# eink_r1.net
KiCad netlist of a schematic drawn in Altium Designer
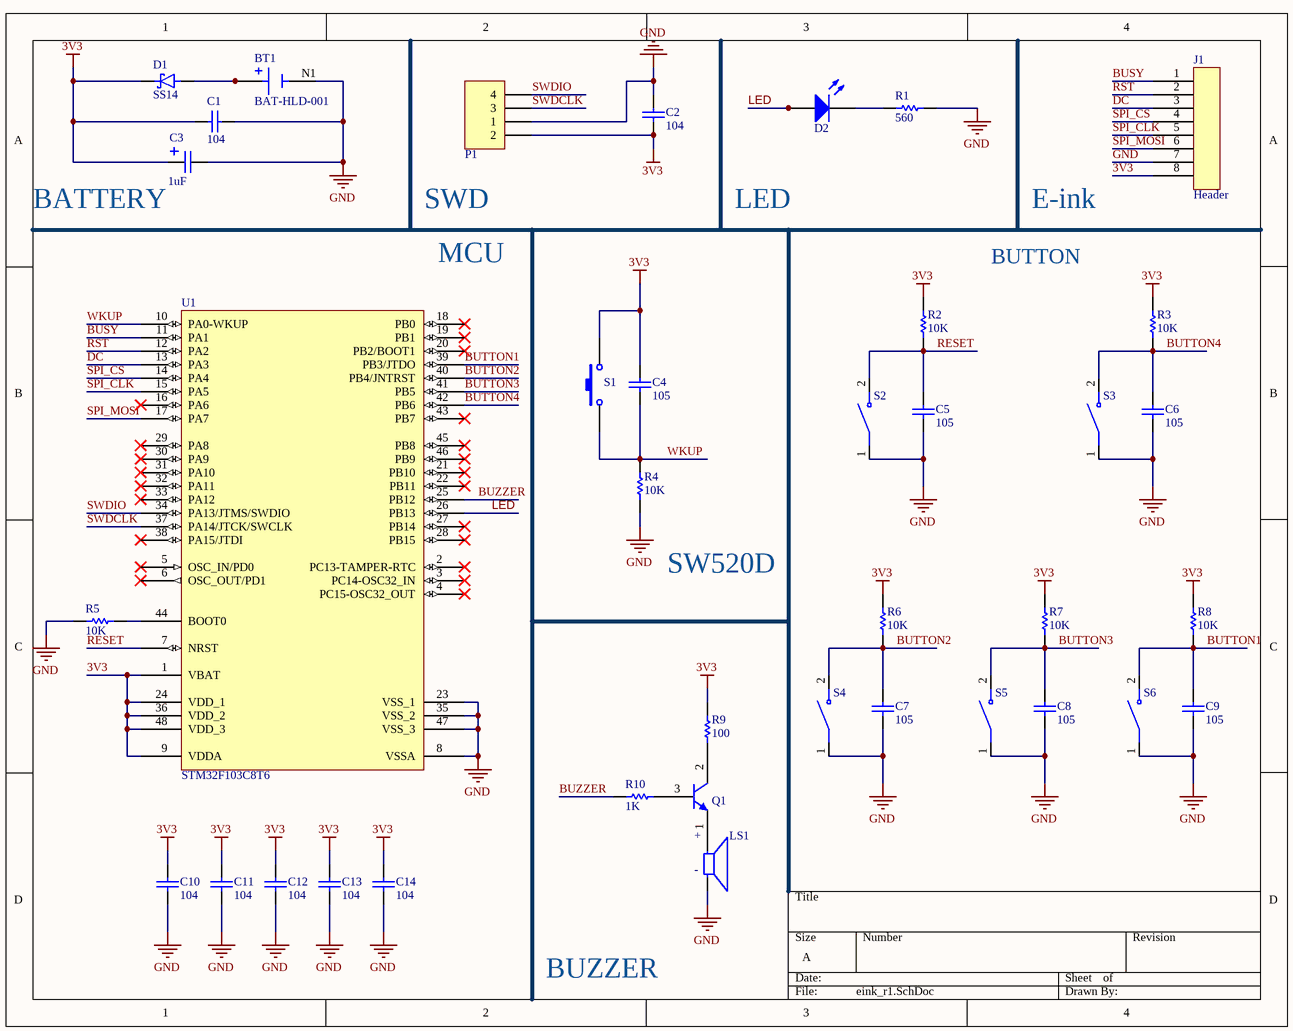
[diagram p0: eink_r1.SchDoc]

(export (version "E")
  (design (tool "Eeschema 10.0.6"))
  (components
    (comp (ref "BT1")
      (value "BAT-HLD-001")
      (footprint "BAT_BAT-HLD-001")
      (description "Battery Retainer Coin, 20.0mm 1 Cell SMD (SMT) Tab")
      (libsource (lib "BAT-HLD-001") (part "BAT-HLD-001"))
    )
    (comp (ref "C1")
      (value "104")
      (footprint "CAP-SM-0603")
      (description "Capacitor")
      (fields (field (name "Comment") "Cap Non-Pol SMD"))
      (libsource (lib "PIF_Library") (part "Cap Non-Pol SMD"))
    )
    (comp (ref "C2")
      (value "104")
      (footprint "CAP-SM-0603")
      (description "Capacitor")
      (fields (field (name "Comment") "Cap Non-Pol SMD"))
      (libsource (lib "PIF_Library") (part "Cap Non-Pol SMD"))
    )
    (comp (ref "C3")
      (value "1uF")
      (footprint "CAPMP3216X18N")
      (fields (field (name "Comment") "Tantalum Capacitor"))
      (libsource (lib "MiclsLib") (part "Tantalum Capacitor"))
    )
    (comp (ref "C4")
      (value "105")
      (footprint "CAP-SM-0603")
      (description "Capacitor")
      (fields (field (name "Comment") "Cap Non-Pol SMD"))
      (libsource (lib "PIF_Library") (part "Cap Non-Pol SMD"))
    )
    (comp (ref "C5")
      (value "105")
      (footprint "CAP-SM-0603")
      (description "Capacitor")
      (fields (field (name "Comment") "Cap Non-Pol SMD"))
      (libsource (lib "PIF_Library") (part "Cap Non-Pol SMD"))
    )
    (comp (ref "C6")
      (value "105")
      (footprint "CAP-SM-0603")
      (description "Capacitor")
      (fields (field (name "Comment") "Cap Non-Pol SMD"))
      (libsource (lib "PIF_Library") (part "Cap Non-Pol SMD"))
    )
    (comp (ref "C7")
      (value "105")
      (footprint "CAP-SM-0603")
      (description "Capacitor")
      (fields (field (name "Comment") "Cap Non-Pol SMD"))
      (libsource (lib "PIF_Library") (part "Cap Non-Pol SMD"))
    )
    (comp (ref "C8")
      (value "105")
      (footprint "CAP-SM-0603")
      (description "Capacitor")
      (fields (field (name "Comment") "Cap Non-Pol SMD"))
      (libsource (lib "PIF_Library") (part "Cap Non-Pol SMD"))
    )
    (comp (ref "C9")
      (value "105")
      (footprint "CAP-SM-0603")
      (description "Capacitor")
      (fields (field (name "Comment") "Cap Non-Pol SMD"))
      (libsource (lib "PIF_Library") (part "Cap Non-Pol SMD"))
    )
    (comp (ref "C10")
      (value "104")
      (footprint "CAP-SM-0603")
      (description "Capacitor")
      (fields (field (name "Comment") "Cap Non-Pol SMD"))
      (libsource (lib "PIF_Library") (part "Cap Non-Pol SMD"))
    )
    (comp (ref "C11")
      (value "104")
      (footprint "CAP-SM-0603")
      (description "Capacitor")
      (fields (field (name "Comment") "Cap Non-Pol SMD"))
      (libsource (lib "PIF_Library") (part "Cap Non-Pol SMD"))
    )
    (comp (ref "C12")
      (value "104")
      (footprint "CAP-SM-0603")
      (description "Capacitor")
      (fields (field (name "Comment") "Cap Non-Pol SMD"))
      (libsource (lib "PIF_Library") (part "Cap Non-Pol SMD"))
    )
    (comp (ref "C13")
      (value "104")
      (footprint "CAP-SM-0603")
      (description "Capacitor")
      (fields (field (name "Comment") "Cap Non-Pol SMD"))
      (libsource (lib "PIF_Library") (part "Cap Non-Pol SMD"))
    )
    (comp (ref "C14")
      (value "104")
      (footprint "CAP-SM-0603")
      (description "Capacitor")
      (fields (field (name "Comment") "Cap Non-Pol SMD"))
      (libsource (lib "PIF_Library") (part "Cap Non-Pol SMD"))
    )
    (comp (ref "D1") (value "SS14") (footprint "DIOM4325X250N") (libsource (lib "SS14") (part "SS14")))
    (comp (ref "D2")
      (value "LED SMD")
      (footprint "LED_0603_Blue")
      (description "LED")
      (libsource (lib "PIF_Library") (part "LED SMD"))
    )
    (comp (ref "J1")
      (value "Header")
      (footprint "PCBComponent_1")
      (description "XH 2.54mm PCB Header 8 Pin SMD Horizontal")
      (libsource (lib "XH-8A_SMD_Header") (part "Header"))
    )
    (comp (ref "LS1")
      (value "CMT-0926-86-SMT-TR")
      (footprint "XDCR_CMT-0926-86-SMT-TR")
      (libsource (lib "CMT-0926-86-SMT-TR") (part "CMT-0926-86-SMT-TR"))
    )
    (comp (ref "P1")
      (value "Header 4H")
      (footprint "JP4H")
      (description "Header, 4-Pin, Right Angle")
      (fields (field (name "PUBLISHER") "Altium Limited"))
      (libsource (lib "PIF_Library") (part "Header 4H"))
    )
    (comp (ref "Q1")
      (value "C1815")
      (footprint "SOT23B")
      (description "NPN Bipolar Transistor")
      (libsource (lib "PIF_Library") (part "C1815"))
    )
    (comp (ref "R1")
      (value "560")
      (footprint "RES-SM-0603")
      (description "Resistor")
      (fields (field (name "Comment") "RESISTOR SMD"))
      (libsource (lib "PIF_Library") (part "RESISTOR SMD"))
    )
    (comp (ref "R2")
      (value "10K")
      (footprint "RES-SM-0603")
      (description "Resistor")
      (fields (field (name "Comment") "RESISTOR SMD"))
      (libsource (lib "PIF_Library") (part "RESISTOR SMD"))
    )
    (comp (ref "R3")
      (value "10K")
      (footprint "RES-SM-0603")
      (description "Resistor")
      (fields (field (name "Comment") "RESISTOR SMD"))
      (libsource (lib "PIF_Library") (part "RESISTOR SMD"))
    )
    (comp (ref "R4")
      (value "10K")
      (footprint "RES-SM-0603")
      (description "Resistor")
      (fields (field (name "Comment") "RESISTOR SMD"))
      (libsource (lib "PIF_Library") (part "RESISTOR SMD"))
    )
    (comp (ref "R5")
      (value "10K")
      (footprint "RES-SM-0603")
      (description "Resistor")
      (fields (field (name "Comment") "RESISTOR SMD"))
      (libsource (lib "PIF_Library") (part "RESISTOR SMD"))
    )
    (comp (ref "R6")
      (value "10K")
      (footprint "RES-SM-0603")
      (description "Resistor")
      (fields (field (name "Comment") "RESISTOR SMD"))
      (libsource (lib "PIF_Library") (part "RESISTOR SMD"))
    )
    (comp (ref "R7")
      (value "10K")
      (footprint "RES-SM-0603")
      (description "Resistor")
      (fields (field (name "Comment") "RESISTOR SMD"))
      (libsource (lib "PIF_Library") (part "RESISTOR SMD"))
    )
    (comp (ref "R8")
      (value "10K")
      (footprint "RES-SM-0603")
      (description "Resistor")
      (fields (field (name "Comment") "RESISTOR SMD"))
      (libsource (lib "PIF_Library") (part "RESISTOR SMD"))
    )
    (comp (ref "R9")
      (value "100")
      (footprint "RES-SM-0603")
      (description "Resistor")
      (fields (field (name "Comment") "RESISTOR SMD"))
      (libsource (lib "PIF_Library") (part "RESISTOR SMD"))
    )
    (comp (ref "R10")
      (value "1K")
      (footprint "RES-SM-0603")
      (description "Resistor")
      (fields (field (name "Comment") "RESISTOR SMD"))
      (libsource (lib "PIF_Library") (part "RESISTOR SMD"))
    )
    (comp (ref "S1")
      (value "Tact SW - 2Pin")
      (footprint "SW2")
      (description "Switch button 2 pin")
      (libsource (lib "PIF_Library") (part "Tact SW - 2Pin"))
    )
    (comp (ref "S2")
      (value "PTS636_SM43J_SMTR_LFS")
      (footprint "SW_PTS636_SM43J_SMTR_LFS")
      (description "Tactile Switch SPST-NO Top Actuated Surface Mount")
      (libsource (lib "PTS636_SM43J_SMTR_LFS") (part "PTS636_SM43J_SMTR_LFS"))
    )
    (comp (ref "S3")
      (value "PTS636_SM43J_SMTR_LFS")
      (footprint "SW_PTS636_SM43J_SMTR_LFS")
      (description "Tactile Switch SPST-NO Top Actuated Surface Mount")
      (libsource (lib "PTS636_SM43J_SMTR_LFS") (part "PTS636_SM43J_SMTR_LFS"))
    )
    (comp (ref "S4")
      (value "PTS636_SM43J_SMTR_LFS")
      (footprint "SW_PTS636_SM43J_SMTR_LFS")
      (description "Tactile Switch SPST-NO Top Actuated Surface Mount")
      (libsource (lib "PTS636_SM43J_SMTR_LFS") (part "PTS636_SM43J_SMTR_LFS"))
    )
    (comp (ref "S5")
      (value "PTS636_SM43J_SMTR_LFS")
      (footprint "SW_PTS636_SM43J_SMTR_LFS")
      (description "Tactile Switch SPST-NO Top Actuated Surface Mount")
      (libsource (lib "PTS636_SM43J_SMTR_LFS") (part "PTS636_SM43J_SMTR_LFS"))
    )
    (comp (ref "S6")
      (value "PTS636_SM43J_SMTR_LFS")
      (footprint "SW_PTS636_SM43J_SMTR_LFS")
      (description "Tactile Switch SPST-NO Top Actuated Surface Mount")
      (libsource (lib "PTS636_SM43J_SMTR_LFS") (part "PTS636_SM43J_SMTR_LFS"))
    )
    (comp (ref "U1")
      (value "STM32F103C8T6")
      (footprint "TSQFP50P900X900X160-48N")
      (fields (field (name "MANUFACTURER") "ST"))
      (libsource (lib "MiclsLib") (part "STM32F103C8T6"))
    )
  )
  (nets
    (net (code "1") (name "/BUSY") (class "Default")
      (node (ref "J1") (pin "1") (pintype "passive"))
      (node (ref "U1") (pin "11") (pinfunction "PA1_11") (pintype "bidirectional"))
    )
    (net (code "2") (name "/BUTTON1") (class "Default")
      (node (ref "C9") (pin "2") (pinfunction "2_2") (pintype "passive"))
      (node (ref "R8") (pin "1") (pinfunction "1_1") (pintype "passive"))
      (node (ref "S6") (pin "2") (pinfunction "NO_2") (pintype "passive"))
      (node (ref "U1") (pin "39") (pinfunction "PB3/JTDO_39") (pintype "bidirectional"))
    )
    (net (code "3") (name "/BUTTON2") (class "Default")
      (node (ref "C7") (pin "2") (pinfunction "2_2") (pintype "passive"))
      (node (ref "R6") (pin "1") (pinfunction "1_1") (pintype "passive"))
      (node (ref "S4") (pin "2") (pinfunction "NO_2") (pintype "passive"))
      (node (ref "U1") (pin "40") (pinfunction "PB4/JNTRST_40") (pintype "bidirectional"))
    )
    (net (code "4") (name "/BUTTON3") (class "Default")
      (node (ref "C8") (pin "2") (pinfunction "2_2") (pintype "passive"))
      (node (ref "R7") (pin "1") (pinfunction "1_1") (pintype "passive"))
      (node (ref "S5") (pin "2") (pinfunction "NO_2") (pintype "passive"))
      (node (ref "U1") (pin "41") (pinfunction "PB5_41") (pintype "bidirectional"))
    )
    (net (code "5") (name "/BUTTON4") (class "Default")
      (node (ref "C6") (pin "2") (pinfunction "2_2") (pintype "passive"))
      (node (ref "R3") (pin "1") (pinfunction "1_1") (pintype "passive"))
      (node (ref "S3") (pin "2") (pinfunction "NO_2") (pintype "passive"))
      (node (ref "U1") (pin "42") (pinfunction "PB6_42") (pintype "bidirectional"))
    )
    (net (code "6") (name "/BUZZER") (class "Default")
      (node (ref "R10") (pin "1") (pinfunction "1_1") (pintype "passive"))
      (node (ref "U1") (pin "25") (pinfunction "PB12_25") (pintype "bidirectional"))
    )
    (net (code "7") (name "/DC") (class "Default")
      (node (ref "J1") (pin "3") (pintype "passive"))
      (node (ref "U1") (pin "13") (pinfunction "PA3_13") (pintype "bidirectional"))
    )
    (net (code "8") (name "/LED") (class "Default")
      (node (ref "D2") (pin "1") (pinfunction "A_1") (pintype "passive"))
      (node (ref "U1") (pin "26") (pinfunction "PB13_26") (pintype "bidirectional"))
    )
    (net (code "9") (name "/RESET") (class "Default")
      (node (ref "C5") (pin "2") (pinfunction "2_2") (pintype "passive"))
      (node (ref "R2") (pin "1") (pinfunction "1_1") (pintype "passive"))
      (node (ref "S2") (pin "2") (pinfunction "NO_2") (pintype "passive"))
      (node (ref "U1") (pin "7") (pinfunction "NRST_7") (pintype "bidirectional"))
    )
    (net (code "10") (name "/RST") (class "Default")
      (node (ref "J1") (pin "2") (pintype "passive"))
      (node (ref "U1") (pin "12") (pinfunction "PA2_12") (pintype "bidirectional"))
    )
    (net (code "11") (name "/SPI_CLK") (class "Default")
      (node (ref "J1") (pin "5") (pintype "passive"))
      (node (ref "U1") (pin "15") (pinfunction "PA5_15") (pintype "bidirectional"))
    )
    (net (code "12") (name "/SPI_CS") (class "Default")
      (node (ref "J1") (pin "4") (pintype "passive"))
      (node (ref "U1") (pin "14") (pinfunction "PA4_14") (pintype "bidirectional"))
    )
    (net (code "13") (name "/SPI_MOSI") (class "Default")
      (node (ref "J1") (pin "6") (pintype "passive"))
      (node (ref "U1") (pin "17") (pinfunction "PA7_17") (pintype "bidirectional"))
    )
    (net (code "14") (name "/SWDCLK") (class "Default")
      (node (ref "P1") (pin "3") (pinfunction "3_3") (pintype "passive"))
      (node (ref "U1") (pin "37") (pinfunction "PA14/JTCK/SWCLK_37") (pintype "bidirectional"))
    )
    (net (code "15") (name "/SWDIO") (class "Default")
      (node (ref "P1") (pin "4") (pinfunction "4_4") (pintype "passive"))
      (node (ref "U1") (pin "34") (pinfunction "PA13/JTMS/SWDIO_34") (pintype "bidirectional"))
    )
    (net (code "16") (name "/WKUP") (class "Default")
      (node (ref "C4") (pin "1") (pinfunction "1_1") (pintype "passive"))
      (node (ref "R4") (pin "2") (pinfunction "2_2") (pintype "passive"))
      (node (ref "S1") (pin "1") (pinfunction "1_1") (pintype "passive"))
      (node (ref "U1") (pin "10") (pinfunction "PA0-WKUP_10") (pintype "bidirectional"))
    )
    (net (code "17") (name "3V3") (class "Default")
      (node (ref "C1") (pin "2") (pinfunction "2_2") (pintype "passive"))
      (node (ref "C10") (pin "2") (pinfunction "2_2") (pintype "passive"))
      (node (ref "C11") (pin "2") (pinfunction "2_2") (pintype "passive"))
      (node (ref "C12") (pin "2") (pinfunction "2_2") (pintype "passive"))
      (node (ref "C13") (pin "2") (pinfunction "2_2") (pintype "passive"))
      (node (ref "C14") (pin "2") (pinfunction "2_2") (pintype "passive"))
      (node (ref "C2") (pin "2") (pinfunction "2_2") (pintype "passive"))
      (node (ref "C3") (pin "1") (pinfunction "1_1") (pintype "passive"))
      (node (ref "C4") (pin "2") (pinfunction "2_2") (pintype "passive"))
      (node (ref "D1") (pin "C") (pinfunction "K_C") (pintype "passive"))
      (node (ref "J1") (pin "8") (pintype "passive"))
      (node (ref "P1") (pin "2") (pinfunction "2_2") (pintype "passive"))
      (node (ref "R2") (pin "2") (pinfunction "2_2") (pintype "passive"))
      (node (ref "R3") (pin "2") (pinfunction "2_2") (pintype "passive"))
      (node (ref "R6") (pin "2") (pinfunction "2_2") (pintype "passive"))
      (node (ref "R7") (pin "2") (pinfunction "2_2") (pintype "passive"))
      (node (ref "R8") (pin "2") (pinfunction "2_2") (pintype "passive"))
      (node (ref "R9") (pin "2") (pinfunction "2_2") (pintype "passive"))
      (node (ref "S1") (pin "2") (pinfunction "2_2") (pintype "passive"))
      (node (ref "U1") (pin "1") (pinfunction "VBAT_1") (pintype "power_in"))
      (node (ref "U1") (pin "24") (pinfunction "VDD_1_24") (pintype "power_in"))
      (node (ref "U1") (pin "36") (pinfunction "VDD_2_36") (pintype "power_in"))
      (node (ref "U1") (pin "48") (pinfunction "VDD_3_48") (pintype "power_in"))
      (node (ref "U1") (pin "9") (pinfunction "VDDA_9") (pintype "power_in"))
    )
    (net (code "18") (name "GND") (class "Default")
      (node (ref "BT1") (pin "N1") (pinfunction "NEG_N1") (pintype "passive"))
      (node (ref "C1") (pin "1") (pinfunction "1_1") (pintype "passive"))
      (node (ref "C10") (pin "1") (pinfunction "1_1") (pintype "passive"))
      (node (ref "C11") (pin "1") (pinfunction "1_1") (pintype "passive"))
      (node (ref "C12") (pin "1") (pinfunction "1_1") (pintype "passive"))
      (node (ref "C13") (pin "1") (pinfunction "1_1") (pintype "passive"))
      (node (ref "C14") (pin "1") (pinfunction "1_1") (pintype "passive"))
      (node (ref "C2") (pin "1") (pinfunction "1_1") (pintype "passive"))
      (node (ref "C3") (pin "2") (pinfunction "2_2") (pintype "passive"))
      (node (ref "C5") (pin "1") (pinfunction "1_1") (pintype "passive"))
      (node (ref "C6") (pin "1") (pinfunction "1_1") (pintype "passive"))
      (node (ref "C7") (pin "1") (pinfunction "1_1") (pintype "passive"))
      (node (ref "C8") (pin "1") (pinfunction "1_1") (pintype "passive"))
      (node (ref "C9") (pin "1") (pinfunction "1_1") (pintype "passive"))
      (node (ref "J1") (pin "7") (pintype "passive"))
      (node (ref "LS1") (pin "N") (pinfunction "N_N") (pintype "passive"))
      (node (ref "P1") (pin "1") (pinfunction "1_1") (pintype "passive"))
      (node (ref "R1") (pin "2") (pinfunction "2_2") (pintype "passive"))
      (node (ref "R4") (pin "1") (pinfunction "1_1") (pintype "passive"))
      (node (ref "R5") (pin "2") (pinfunction "2_2") (pintype "passive"))
      (node (ref "S2") (pin "1") (pinfunction "COM_1") (pintype "passive"))
      (node (ref "S3") (pin "1") (pinfunction "COM_1") (pintype "passive"))
      (node (ref "S4") (pin "1") (pinfunction "COM_1") (pintype "passive"))
      (node (ref "S5") (pin "1") (pinfunction "COM_1") (pintype "passive"))
      (node (ref "S6") (pin "1") (pinfunction "COM_1") (pintype "passive"))
      (node (ref "U1") (pin "23") (pinfunction "VSS_1_23") (pintype "power_in"))
      (node (ref "U1") (pin "35") (pinfunction "VSS_2_35") (pintype "power_in"))
      (node (ref "U1") (pin "47") (pinfunction "VSS_3_47") (pintype "power_in"))
      (node (ref "U1") (pin "8") (pinfunction "VSSA_8") (pintype "power_in"))
    )
    (net (code "19") (name "Net-(BT1-POS-PadP1)") (class "Default")
      (node (ref "BT1") (pin "P1") (pinfunction "POS_P1") (pintype "passive"))
      (node (ref "BT1") (pin "P2") (pinfunction "POS_P2") (pintype "passive"))
      (node (ref "D1") (pin "A") (pinfunction "A_A") (pintype "passive"))
    )
    (net (code "20") (name "Net-(D2-K)") (class "Default")
      (node (ref "D2") (pin "2") (pinfunction "K_2") (pintype "passive"))
      (node (ref "R1") (pin "1") (pinfunction "1_1") (pintype "passive"))
    )
    (net (code "21") (name "Net-(Q1-B)") (class "Default")
      (node (ref "Q1") (pin "3") (pinfunction "B_3") (pintype "passive"))
      (node (ref "R10") (pin "2") (pinfunction "2_2") (pintype "passive"))
    )
    (net (code "22") (name "Net-(Q1-C)") (class "Default")
      (node (ref "Q1") (pin "2") (pinfunction "C_2") (pintype "passive"))
      (node (ref "R9") (pin "1") (pinfunction "1_1") (pintype "passive"))
    )
    (net (code "23") (name "Net-(Q1-E)") (class "Default")
      (node (ref "LS1") (pin "P") (pinfunction "P_P") (pintype "passive"))
      (node (ref "Q1") (pin "1") (pinfunction "E_1") (pintype "passive"))
    )
    (net (code "24") (name "Net-(U1-BOOT0)") (class "Default")
      (node (ref "R5") (pin "1") (pinfunction "1_1") (pintype "passive"))
      (node (ref "U1") (pin "44") (pinfunction "BOOT0_44") (pintype "passive"))
    )
    (net (code "25") (name "unconnected-(U1-OSC_IN{slash}PD0-Pad5)") (class "Default")
      (node (ref "U1") (pin "5") (pinfunction "OSC_IN/PD0_5") (pintype "input+no_connect"))
    )
    (net (code "26") (name "unconnected-(U1-OSC_OUT{slash}PD1-Pad6)") (class "Default")
      (node (ref "U1") (pin "6") (pinfunction "OSC_OUT/PD1_6") (pintype "output+no_connect"))
    )
    (net (code "27") (name "unconnected-(U1-PA6-Pad16)") (class "Default")
      (node (ref "U1") (pin "16") (pinfunction "PA6_16") (pintype "bidirectional+no_connect"))
    )
    (net (code "28") (name "unconnected-(U1-PA8-Pad29)") (class "Default")
      (node (ref "U1") (pin "29") (pinfunction "PA8_29") (pintype "bidirectional+no_connect"))
    )
    (net (code "29") (name "unconnected-(U1-PA9-Pad30)") (class "Default")
      (node (ref "U1") (pin "30") (pinfunction "PA9_30") (pintype "bidirectional+no_connect"))
    )
    (net (code "30") (name "unconnected-(U1-PA10-Pad31)") (class "Default")
      (node (ref "U1") (pin "31") (pinfunction "PA10_31") (pintype "bidirectional+no_connect"))
    )
    (net (code "31") (name "unconnected-(U1-PA11-Pad32)") (class "Default")
      (node (ref "U1") (pin "32") (pinfunction "PA11_32") (pintype "bidirectional+no_connect"))
    )
    (net (code "32") (name "unconnected-(U1-PA12-Pad33)") (class "Default")
      (node (ref "U1") (pin "33") (pinfunction "PA12_33") (pintype "bidirectional+no_connect"))
    )
    (net (code "33") (name "unconnected-(U1-PA15{slash}JTDI-Pad38)") (class "Default")
      (node (ref "U1") (pin "38") (pinfunction "PA15/JTDI_38") (pintype "bidirectional+no_connect"))
    )
    (net (code "34") (name "unconnected-(U1-PB0-Pad18)") (class "Default")
      (node (ref "U1") (pin "18") (pinfunction "PB0_18") (pintype "bidirectional+no_connect"))
    )
    (net (code "35") (name "unconnected-(U1-PB1-Pad19)") (class "Default")
      (node (ref "U1") (pin "19") (pinfunction "PB1_19") (pintype "bidirectional+no_connect"))
    )
    (net (code "36") (name "unconnected-(U1-PB2{slash}BOOT1-Pad20)") (class "Default")
      (node (ref "U1") (pin "20") (pinfunction "PB2/BOOT1_20") (pintype "bidirectional+no_connect"))
    )
    (net (code "37") (name "unconnected-(U1-PB7-Pad43)") (class "Default")
      (node (ref "U1") (pin "43") (pinfunction "PB7_43") (pintype "bidirectional+no_connect"))
    )
    (net (code "38") (name "unconnected-(U1-PB8-Pad45)") (class "Default")
      (node (ref "U1") (pin "45") (pinfunction "PB8_45") (pintype "bidirectional+no_connect"))
    )
    (net (code "39") (name "unconnected-(U1-PB9-Pad46)") (class "Default")
      (node (ref "U1") (pin "46") (pinfunction "PB9_46") (pintype "bidirectional+no_connect"))
    )
    (net (code "40") (name "unconnected-(U1-PB10-Pad21)") (class "Default")
      (node (ref "U1") (pin "21") (pinfunction "PB10_21") (pintype "bidirectional+no_connect"))
    )
    (net (code "41") (name "unconnected-(U1-PB11-Pad22)") (class "Default")
      (node (ref "U1") (pin "22") (pinfunction "PB11_22") (pintype "bidirectional+no_connect"))
    )
    (net (code "42") (name "unconnected-(U1-PB14-Pad27)") (class "Default")
      (node (ref "U1") (pin "27") (pinfunction "PB14_27") (pintype "bidirectional+no_connect"))
    )
    (net (code "43") (name "unconnected-(U1-PB15-Pad28)") (class "Default")
      (node (ref "U1") (pin "28") (pinfunction "PB15_28") (pintype "bidirectional+no_connect"))
    )
    (net (code "44") (name "unconnected-(U1-PC13-TAMPER-RTC-Pad2)") (class "Default")
      (node (ref "U1") (pin "2") (pinfunction "PC13-TAMPER-RTC_2") (pintype "bidirectional+no_connect"))
    )
    (net (code "45") (name "unconnected-(U1-PC14-OSC32_IN-Pad3)") (class "Default")
      (node (ref "U1") (pin "3") (pinfunction "PC14-OSC32_IN_3") (pintype "bidirectional+no_connect"))
    )
    (net (code "46") (name "unconnected-(U1-PC15-OSC32_OUT-Pad4)") (class "Default")
      (node (ref "U1") (pin "4") (pinfunction "PC15-OSC32_OUT_4") (pintype "bidirectional+no_connect"))
    )
  )
)
